# divisor-de-tension.net
KiCad netlist of a schematic drawn in EAGLE
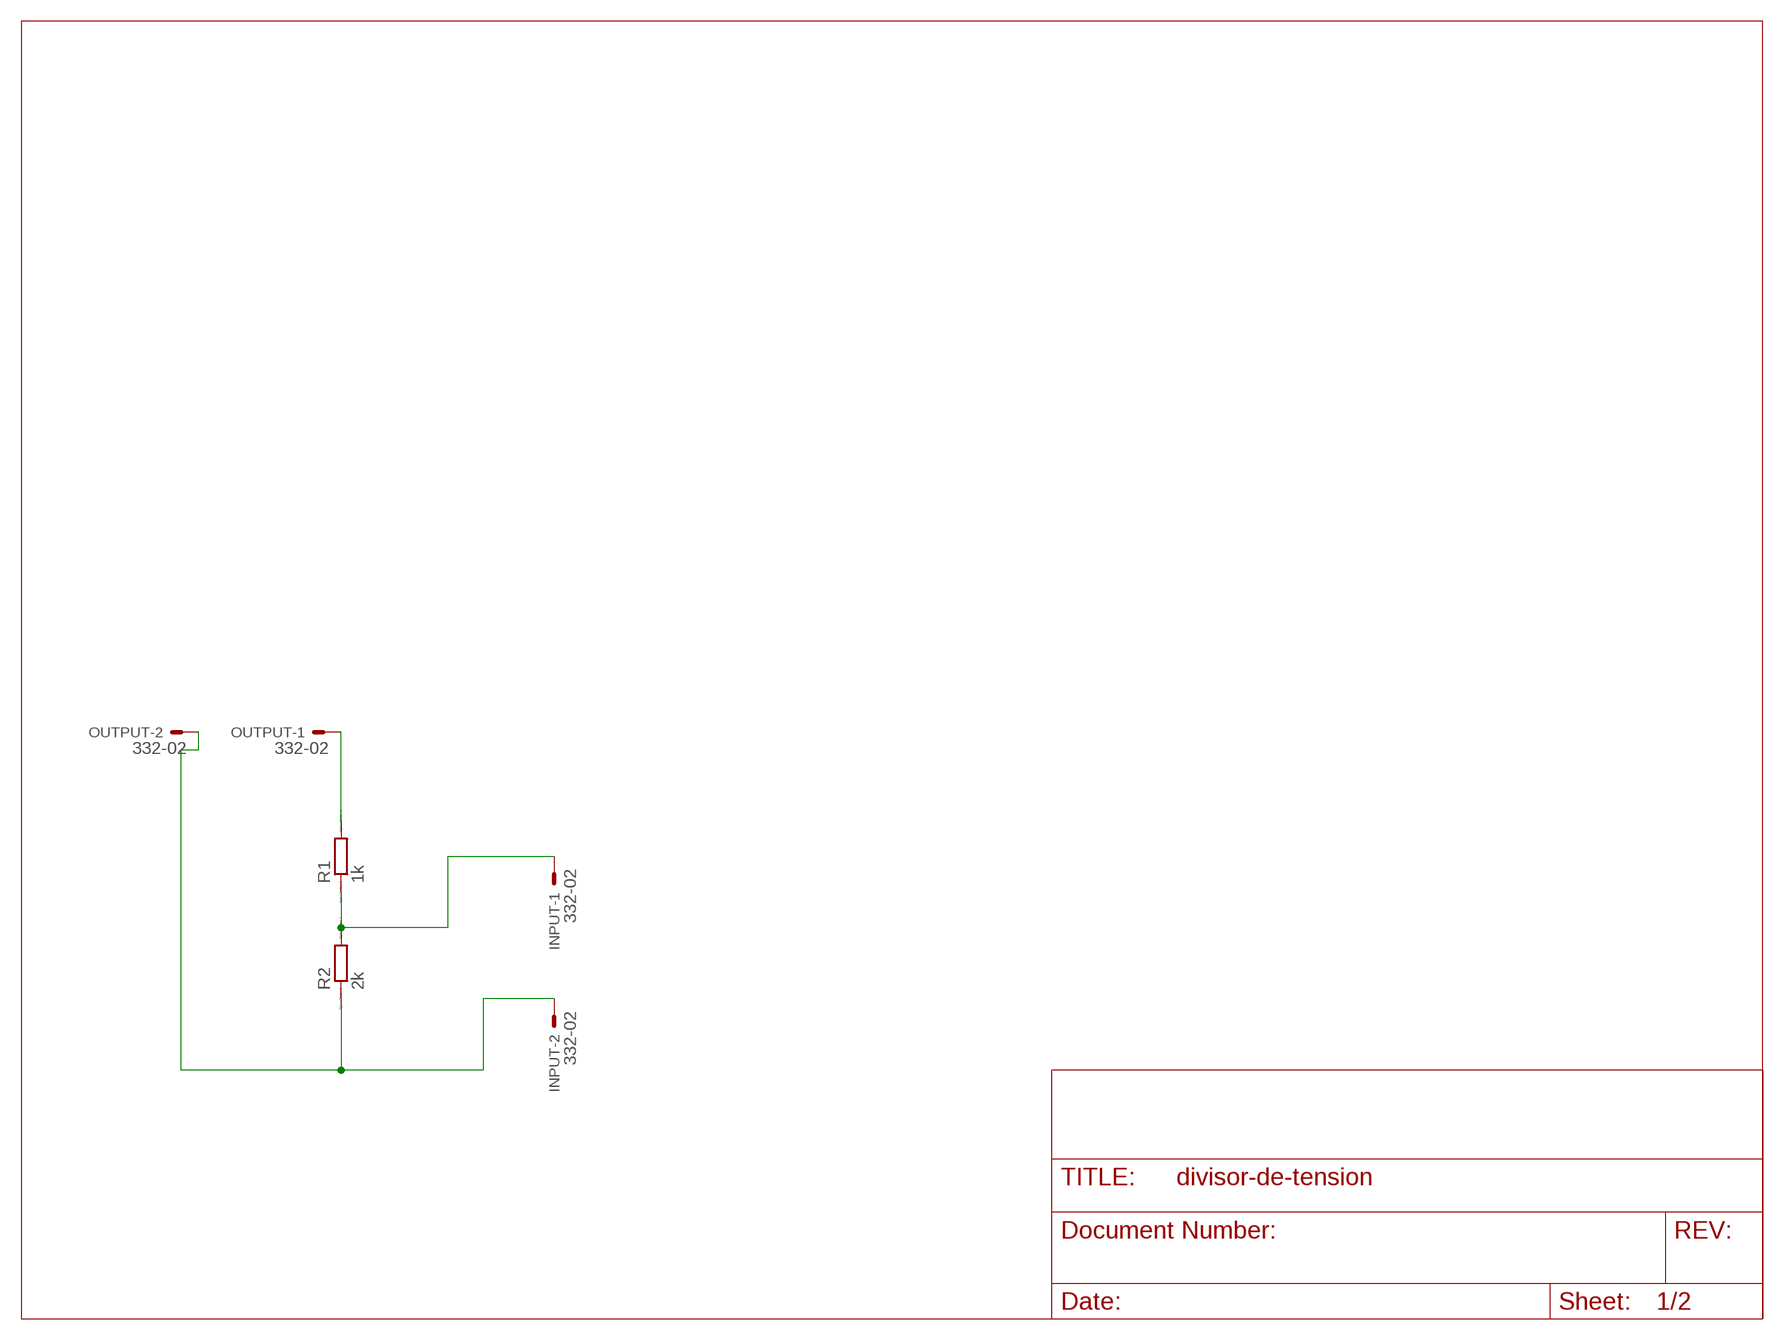
[diagram p0: schematic, sheet 1]

(export (version "E")
  (design (tool "Eeschema 10.0.6"))
  (components
    (comp (ref "INPUT")
      (value "332-02")
      (footprint "eagle-import:332-02")
      (libsource (lib "eagle-import") (part "332-02"))
    )
    (comp (ref "OUTPUT")
      (value "332-02")
      (footprint "eagle-import:332-02")
      (libsource (lib "eagle-import") (part "332-02"))
    )
    (comp (ref "R1")
      (value "1k")
      (footprint "eagle-import:0207_10")
      (libsource (lib "eagle-import") (part "R0207/10"))
    )
    (comp (ref "R2")
      (value "2k")
      (footprint "eagle-import:0207_10")
      (libsource (lib "eagle-import") (part "R0207/10"))
    )
  )
  (nets
    (net (code "1") (name "Net-(INPUTA-S)") (class "Default")
      (node (ref "INPUT") (pin "1") (pinfunction "S_1") (pintype "passive"))
      (node (ref "R1") (pin "1") (pinfunction "1_1") (pintype "passive"))
      (node (ref "R2") (pin "2") (pinfunction "2_2") (pintype "passive"))
    )
    (net (code "2") (name "Net-(INPUTB-S)") (class "Default")
      (node (ref "INPUT") (pin "2") (pinfunction "S_2") (pintype "passive"))
      (node (ref "OUTPUT") (pin "2") (pinfunction "S_2") (pintype "passive"))
      (node (ref "R2") (pin "1") (pinfunction "1_1") (pintype "passive"))
    )
    (net (code "3") (name "Net-(OUTPUTA-S)") (class "Default")
      (node (ref "OUTPUT") (pin "1") (pinfunction "S_1") (pintype "passive"))
      (node (ref "R1") (pin "2") (pinfunction "2_2") (pintype "passive"))
    )
  )
)
